# LEDsAndButtons.net
KiCad netlist of a schematic drawn in Altium Designer
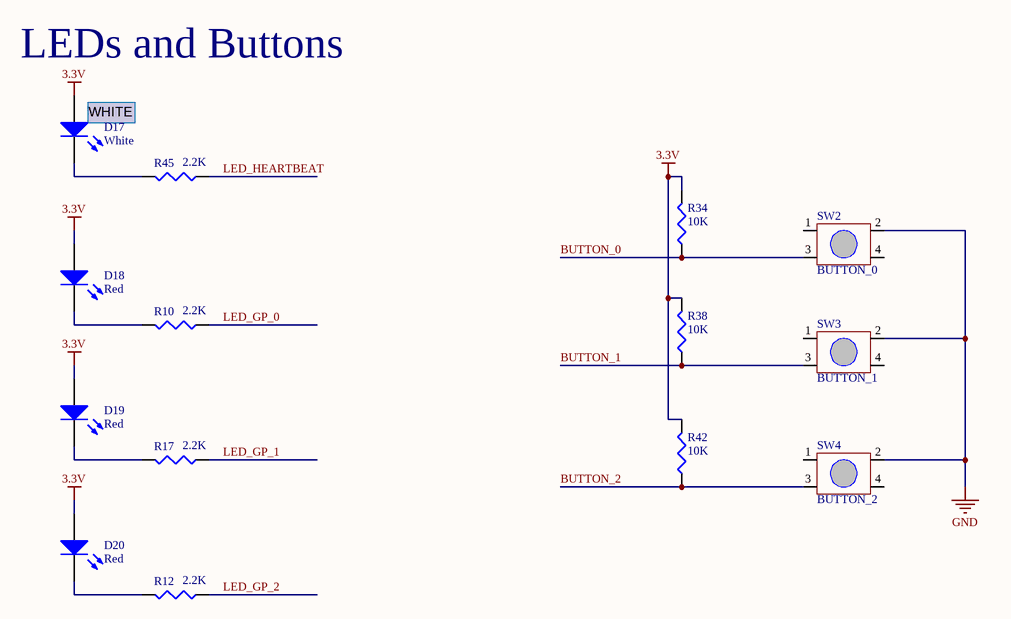
[diagram p0: LEDsAndButtons.SchDoc]

(export (version "E")
  (design (tool "Eeschema 10.0.6"))
  (components
    (comp (ref "D17") (value "White") (footprint "SurfaceMount(603)") (libsource (lib "mrone") (part "LED")))
    (comp (ref "D18") (value "Red") (footprint "SurfaceMount(603)") (libsource (lib "mrone") (part "LED")))
    (comp (ref "D19") (value "Red") (footprint "SurfaceMount(603)") (libsource (lib "mrone") (part "LED")))
    (comp (ref "D20") (value "Red") (footprint "SurfaceMount(603)") (libsource (lib "mrone") (part "LED")))
    (comp (ref "R10")
      (value "2.2K")
      (footprint "RESC1608L")
      (description "Resistor")
      (fields (field (name "Comment") "Res3") (field (name "PUBLISHER") "Altium Limited"))
      (libsource (lib "Miscellaneous Devices") (part "Res3"))
    )
    (comp (ref "R12")
      (value "2.2K")
      (footprint "RESC1608L")
      (description "Resistor")
      (fields (field (name "Comment") "Res3") (field (name "PUBLISHER") "Altium Limited"))
      (libsource (lib "Miscellaneous Devices") (part "Res3"))
    )
    (comp (ref "R17")
      (value "2.2K")
      (footprint "RESC1608L")
      (description "Resistor")
      (fields (field (name "Comment") "Res3") (field (name "PUBLISHER") "Altium Limited"))
      (libsource (lib "Miscellaneous Devices") (part "Res3"))
    )
    (comp (ref "R34")
      (value "10K")
      (footprint "RESC1608L")
      (description "Resistor")
      (fields (field (name "Comment") "Res3") (field (name "PUBLISHER") "Altium Limited"))
      (libsource (lib "Miscellaneous Devices") (part "Res3"))
    )
    (comp (ref "R38")
      (value "10K")
      (footprint "RESC1608L")
      (description "Resistor")
      (fields (field (name "Comment") "Res3") (field (name "PUBLISHER") "Altium Limited"))
      (libsource (lib "Miscellaneous Devices") (part "Res3"))
    )
    (comp (ref "R42")
      (value "10K")
      (footprint "RESC1608L")
      (description "Resistor")
      (fields (field (name "Comment") "Res3") (field (name "PUBLISHER") "Altium Limited"))
      (libsource (lib "Miscellaneous Devices") (part "Res3"))
    )
    (comp (ref "R45")
      (value "2.2K")
      (footprint "RESC1608L")
      (description "Resistor")
      (fields (field (name "Comment") "Res3") (field (name "PUBLISHER") "Altium Limited"))
      (libsource (lib "Miscellaneous Devices") (part "Res3"))
    )
    (comp (ref "SW2")
      (value "BUTTON_0")
      (footprint "SwitchTall-TL330")
      (libsource (lib "mrone") (part "Switch-TL330"))
    )
    (comp (ref "SW3")
      (value "BUTTON_1")
      (footprint "SwitchTall-TL330")
      (libsource (lib "mrone") (part "Switch-TL330"))
    )
    (comp (ref "SW4")
      (value "BUTTON_2")
      (footprint "SwitchTall-TL330")
      (libsource (lib "mrone") (part "Switch-TL330"))
    )
  )
  (nets
    (net (code "1") (name "/BUTTON_0") (class "Default")
      (node (ref "R34") (pin "1") (pinfunction "1_1") (pintype "passive"))
      (node (ref "SW2") (pin "3") (pinfunction "3_3") (pintype "passive"))
    )
    (net (code "2") (name "/BUTTON_1") (class "Default")
      (node (ref "R38") (pin "1") (pinfunction "1_1") (pintype "passive"))
      (node (ref "SW3") (pin "3") (pinfunction "3_3") (pintype "passive"))
    )
    (net (code "3") (name "/BUTTON_2") (class "Default")
      (node (ref "R42") (pin "1") (pinfunction "1_1") (pintype "passive"))
      (node (ref "SW4") (pin "3") (pinfunction "3_3") (pintype "passive"))
    )
    (net (code "4") (name "/LED_GP_0") (class "Default")
      (node (ref "R10") (pin "1") (pinfunction "1_1") (pintype "passive"))
    )
    (net (code "5") (name "/LED_GP_1") (class "Default")
      (node (ref "R17") (pin "1") (pinfunction "1_1") (pintype "passive"))
    )
    (net (code "6") (name "/LED_GP_2") (class "Default")
      (node (ref "R12") (pin "1") (pinfunction "1_1") (pintype "passive"))
    )
    (net (code "7") (name "/LED_HEARTBEAT") (class "Default")
      (node (ref "R45") (pin "1") (pinfunction "1_1") (pintype "passive"))
    )
    (net (code "8") (name "3.3V") (class "Default")
      (node (ref "D17") (pin "1") (pinfunction "A_1") (pintype "passive"))
      (node (ref "D18") (pin "1") (pinfunction "A_1") (pintype "passive"))
      (node (ref "D19") (pin "1") (pinfunction "A_1") (pintype "passive"))
      (node (ref "D20") (pin "1") (pinfunction "A_1") (pintype "passive"))
      (node (ref "R34") (pin "2") (pinfunction "2_2") (pintype "passive"))
      (node (ref "R38") (pin "2") (pinfunction "2_2") (pintype "passive"))
      (node (ref "R42") (pin "2") (pinfunction "2_2") (pintype "passive"))
    )
    (net (code "9") (name "GND") (class "Default")
      (node (ref "SW2") (pin "2") (pinfunction "2_2") (pintype "passive"))
      (node (ref "SW3") (pin "2") (pinfunction "2_2") (pintype "passive"))
      (node (ref "SW4") (pin "2") (pinfunction "2_2") (pintype "passive"))
    )
    (net (code "10") (name "Net-(D17-K)") (class "Default")
      (node (ref "D17") (pin "2") (pinfunction "K_2") (pintype "passive"))
      (node (ref "R45") (pin "2") (pinfunction "2_2") (pintype "passive"))
    )
    (net (code "11") (name "Net-(D18-K)") (class "Default")
      (node (ref "D18") (pin "2") (pinfunction "K_2") (pintype "passive"))
      (node (ref "R10") (pin "2") (pinfunction "2_2") (pintype "passive"))
    )
    (net (code "12") (name "Net-(D19-K)") (class "Default")
      (node (ref "D19") (pin "2") (pinfunction "K_2") (pintype "passive"))
      (node (ref "R17") (pin "2") (pinfunction "2_2") (pintype "passive"))
    )
    (net (code "13") (name "Net-(D20-K)") (class "Default")
      (node (ref "D20") (pin "2") (pinfunction "K_2") (pintype "passive"))
      (node (ref "R12") (pin "2") (pinfunction "2_2") (pintype "passive"))
    )
    (net (code "14") (name "unconnected-(SW2-Pad1)") (class "Default")
      (node (ref "SW2") (pin "1") (pinfunction "1_1") (pintype "passive"))
    )
    (net (code "15") (name "unconnected-(SW2-Pad4)") (class "Default")
      (node (ref "SW2") (pin "4") (pinfunction "4_4") (pintype "passive"))
    )
    (net (code "16") (name "unconnected-(SW3-Pad1)") (class "Default")
      (node (ref "SW3") (pin "1") (pinfunction "1_1") (pintype "passive"))
    )
    (net (code "17") (name "unconnected-(SW3-Pad4)") (class "Default")
      (node (ref "SW3") (pin "4") (pinfunction "4_4") (pintype "passive"))
    )
    (net (code "18") (name "unconnected-(SW4-Pad1)") (class "Default")
      (node (ref "SW4") (pin "1") (pinfunction "1_1") (pintype "passive"))
    )
    (net (code "19") (name "unconnected-(SW4-Pad4)") (class "Default")
      (node (ref "SW4") (pin "4") (pinfunction "4_4") (pintype "passive"))
    )
  )
)
